# Sheet1.net
KiCad netlist of a schematic drawn in Altium Designer
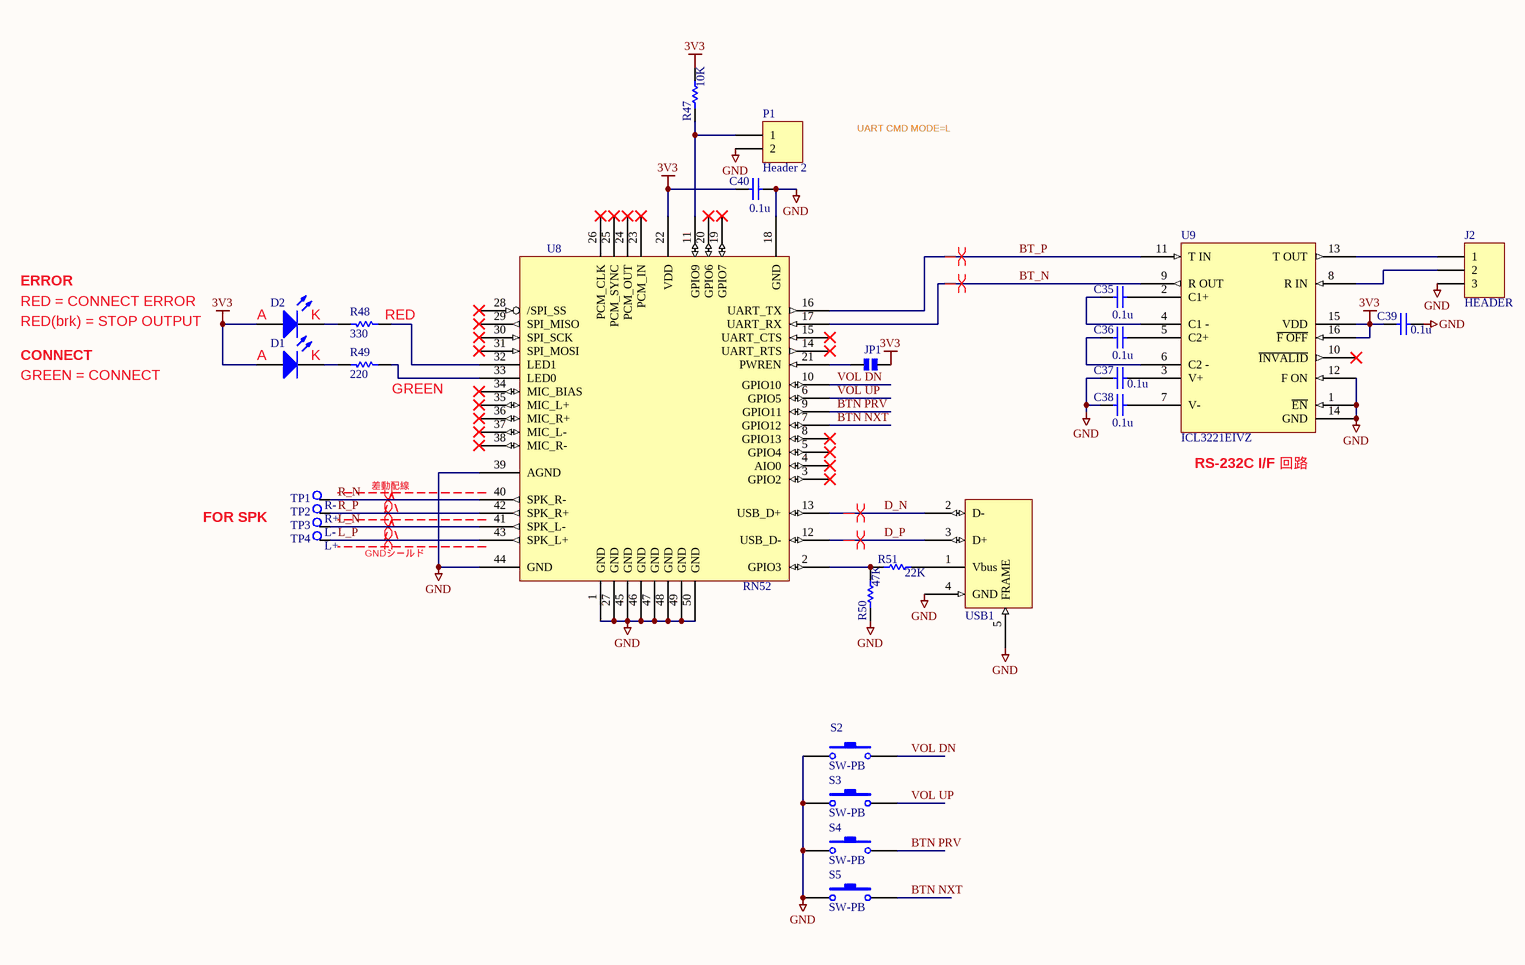
[diagram p0: Sheet1.SchDoc]

(export (version "E")
  (design (tool "Eeschema 10.0.6"))
  (components
    (comp (ref "C35")
      (value "0.1u")
      (footprint "1608[0603]")
      (description "Capacitor (Semiconductor SIM Model)")
      (fields (field (name "PUBLISHER") "Altium Limited"))
      (libsource (lib "Miscellaneous Devices") (part "Cap Semi"))
    )
    (comp (ref "C36")
      (value "0.1u")
      (footprint "1608[0603]")
      (description "Capacitor (Semiconductor SIM Model)")
      (fields (field (name "PUBLISHER") "Altium Limited"))
      (libsource (lib "Miscellaneous Devices") (part "Cap Semi"))
    )
    (comp (ref "C37")
      (value "0.1u")
      (footprint "1608[0603]")
      (description "Capacitor (Semiconductor SIM Model)")
      (fields (field (name "PUBLISHER") "Altium Limited"))
      (libsource (lib "Miscellaneous Devices") (part "Cap Semi"))
    )
    (comp (ref "C38")
      (value "0.1u")
      (footprint "1608[0603]")
      (description "Capacitor (Semiconductor SIM Model)")
      (fields (field (name "PUBLISHER") "Altium Limited"))
      (libsource (lib "Miscellaneous Devices") (part "Cap Semi"))
    )
    (comp (ref "C39")
      (value "0.1u")
      (footprint "1608[0603]")
      (description "Capacitor (Semiconductor SIM Model)")
      (fields (field (name "PUBLISHER") "Altium Limited"))
      (libsource (lib "Miscellaneous Devices") (part "Cap Semi"))
    )
    (comp (ref "C40")
      (value "0.1u")
      (footprint "1608[0603]")
      (description "Capacitor (Semiconductor SIM Model)")
      (fields (field (name "PUBLISHER") "Altium Limited"))
      (libsource (lib "Miscellaneous Devices") (part "Cap Semi"))
    )
    (comp (ref "D1")
      (value "LED2")
      (footprint "LED_2012_DIOC2012X08N")
      (description "Typical RED, GREEN, YELLOW, AMBER GaAs LED")
      (fields (field (name "PUBLISHER") "Altium Limited"))
      (libsource (lib "JP_Integrated_lib") (part "LED2"))
    )
    (comp (ref "D2")
      (value "LED2")
      (footprint "LED_2012_DIOC2012X08N")
      (description "Typical RED, GREEN, YELLOW, AMBER GaAs LED")
      (fields (field (name "PUBLISHER") "Altium Limited"))
      (libsource (lib "JP_Integrated_lib") (part "LED2"))
    )
    (comp (ref "J2")
      (value "HEADER")
      (footprint "3x 2.5mm pitch Pad")
      (description "Header, 3-Pin")
      (fields (field (name "PUBLISHER") "Altium Limited"))
      (libsource (lib "Miscellaneous Connectors") (part "Header 3"))
    )
    (comp (ref "JP1") (value "JP4") (footprint "JUMP_PAD") (libsource (lib "ORIGINAL PARTS") (part "JP4")))
    (comp (ref "P1")
      (value "Header 2")
      (footprint "2x 2.5mm pitch Pad")
      (description "Header, 2-Pin")
      (fields (field (name "PUBLISHER") "Altium Limited"))
      (libsource (lib "JP_Integrated_lib") (part "Header 2"))
    )
    (comp (ref "R47")
      (value "10K")
      (footprint "1608[0603]")
      (description "Semiconductor Resistor")
      (fields (field (name "PUBLISHER") "Altium Limited"))
      (libsource (lib "Miscellaneous Devices") (part "Res Semi"))
    )
    (comp (ref "R48")
      (value "330")
      (footprint "1608[0603]")
      (description "Resistor")
      (libsource (lib "Miscellaneous Devices") (part "Res1"))
    )
    (comp (ref "R49")
      (value "220")
      (footprint "1608[0603]")
      (description "Resistor")
      (libsource (lib "Miscellaneous Devices") (part "Res1"))
    )
    (comp (ref "R50")
      (value "47K")
      (footprint "1608[0603]")
      (description "Semiconductor Resistor")
      (fields (field (name "PUBLISHER") "Altium Limited"))
      (libsource (lib "Miscellaneous Devices") (part "Res Semi"))
    )
    (comp (ref "R51")
      (value "22K")
      (footprint "1608[0603]")
      (description "Semiconductor Resistor")
      (fields (field (name "PUBLISHER") "Altium Limited"))
      (libsource (lib "Miscellaneous Devices") (part "Res Semi"))
    )
    (comp (ref "S2")
      (value "SW-PB")
      (footprint "TACT_SW")
      (description "Switch")
      (fields (field (name "PUBLISHER") "Altium Limited"))
      (libsource (lib "JP_Integrated_lib") (part "SW-PB"))
    )
    (comp (ref "S3")
      (value "SW-PB")
      (footprint "TACT_SW")
      (description "Switch")
      (fields (field (name "PUBLISHER") "Altium Limited"))
      (libsource (lib "JP_Integrated_lib") (part "SW-PB"))
    )
    (comp (ref "S4")
      (value "SW-PB")
      (footprint "TACT_SW")
      (description "Switch")
      (fields (field (name "PUBLISHER") "Altium Limited"))
      (libsource (lib "JP_Integrated_lib") (part "SW-PB"))
    )
    (comp (ref "S5")
      (value "SW-PB")
      (footprint "TACT_SW")
      (description "Switch")
      (fields (field (name "PUBLISHER") "Altium Limited"))
      (libsource (lib "JP_Integrated_lib") (part "SW-PB"))
    )
    (comp (ref "TP1") (value "R-") (footprint "PAD1") (libsource (lib "ORIGINAL PARTS") (part "RAUND1")))
    (comp (ref "TP2") (value "R+") (footprint "PAD1") (libsource (lib "ORIGINAL PARTS") (part "RAUND1")))
    (comp (ref "TP3") (value "L-") (footprint "PAD1") (libsource (lib "ORIGINAL PARTS") (part "RAUND1")))
    (comp (ref "TP4") (value "L+") (footprint "PAD1") (libsource (lib "ORIGINAL PARTS") (part "RAUND1")))
    (comp (ref "U8") (value "RN52") (footprint "RN-52") (libsource (lib "ORIGINAL PARTS") (part "RN52")))
    (comp (ref "U9")
      (value "ICL3221EIVZ")
      (footprint "16_TSSOP_TSOP65P640X110-16N")
      (libsource (lib "ORIGINAL PARTS") (part "TRS3221E"))
    )
    (comp (ref "USB1")
      (value "USB002")
      (footprint "USB2.5-2H4C")
      (libsource (lib "ORIGINAL PARTS") (part "USB002"))
    )
  )
  (nets
    (net (code "1") (name "/BTN NXT") (class "Default")
      (node (ref "S5") (pin "2") (pinfunction "2_2") (pintype "passive"))
      (node (ref "U8") (pin "7") (pinfunction "GPIO12_7") (pintype "bidirectional"))
    )
    (net (code "2") (name "/BTN PRV") (class "Default")
      (node (ref "S4") (pin "2") (pinfunction "2_2") (pintype "passive"))
      (node (ref "U8") (pin "9") (pinfunction "GPIO11_9") (pintype "bidirectional"))
    )
    (net (code "3") (name "/BT_N") (class "Default")
      (node (ref "U8") (pin "17") (pinfunction "UART_RX_17") (pintype "input"))
      (node (ref "U9") (pin "9") (pinfunction "R_OUT_9") (pintype "output"))
    )
    (net (code "4") (name "/BT_P") (class "Default")
      (node (ref "U8") (pin "16") (pinfunction "UART_TX_16") (pintype "output"))
      (node (ref "U9") (pin "11") (pinfunction "T_IN_11") (pintype "input"))
    )
    (net (code "5") (name "/D_N") (class "Default")
      (node (ref "U8") (pin "13") (pinfunction "USB_D+_13") (pintype "bidirectional"))
      (node (ref "USB1") (pin "2") (pinfunction "D-_2") (pintype "bidirectional"))
    )
    (net (code "6") (name "/D_P") (class "Default")
      (node (ref "U8") (pin "12") (pinfunction "USB_D-_12") (pintype "bidirectional"))
      (node (ref "USB1") (pin "3") (pinfunction "D+_3") (pintype "bidirectional"))
    )
    (net (code "7") (name "/L_N") (class "Default")
      (node (ref "TP3") (pin "1") (pinfunction "1_1") (pintype "passive"))
      (node (ref "U8") (pin "41") (pinfunction "SPK_L-_41") (pintype "output"))
    )
    (net (code "8") (name "/L_P") (class "Default")
      (node (ref "TP4") (pin "1") (pinfunction "1_1") (pintype "passive"))
      (node (ref "U8") (pin "43") (pinfunction "SPK_L+_43") (pintype "output"))
    )
    (net (code "9") (name "/R_N") (class "Default")
      (node (ref "TP1") (pin "1") (pinfunction "1_1") (pintype "passive"))
      (node (ref "U8") (pin "40") (pinfunction "SPK_R-_40") (pintype "output"))
    )
    (net (code "10") (name "/R_P") (class "Default")
      (node (ref "TP2") (pin "1") (pinfunction "1_1") (pintype "passive"))
      (node (ref "U8") (pin "42") (pinfunction "SPK_R+_42") (pintype "output"))
    )
    (net (code "11") (name "/VOL DN") (class "Default")
      (node (ref "S2") (pin "2") (pinfunction "2_2") (pintype "passive"))
      (node (ref "U8") (pin "10") (pinfunction "GPIO10_10") (pintype "bidirectional"))
    )
    (net (code "12") (name "/VOL UP") (class "Default")
      (node (ref "S3") (pin "2") (pinfunction "2_2") (pintype "passive"))
      (node (ref "U8") (pin "6") (pinfunction "GPIO5_6") (pintype "bidirectional"))
    )
    (net (code "13") (name "3V3") (class "Default")
      (node (ref "C39") (pin "1") (pinfunction "1_1") (pintype "passive"))
      (node (ref "C40") (pin "1") (pinfunction "1_1") (pintype "passive"))
      (node (ref "D1") (pin "1") (pinfunction "A_1") (pintype "passive"))
      (node (ref "D2") (pin "1") (pinfunction "A_1") (pintype "passive"))
      (node (ref "JP1") (pin "2") (pinfunction "2_2") (pintype "passive"))
      (node (ref "R47") (pin "2") (pinfunction "2_2") (pintype "passive"))
      (node (ref "U8") (pin "22") (pinfunction "VDD_22") (pintype "power_in"))
      (node (ref "U9") (pin "15") (pinfunction "VDD_15") (pintype "power_in"))
      (node (ref "U9") (pin "16") (pinfunction "~{F_OFF}_16") (pintype "input"))
    )
    (net (code "14") (name "GND") (class "Default")
      (node (ref "C37") (pin "1") (pinfunction "1_1") (pintype "passive"))
      (node (ref "C38") (pin "1") (pinfunction "1_1") (pintype "passive"))
      (node (ref "C39") (pin "2") (pinfunction "2_2") (pintype "passive"))
      (node (ref "C40") (pin "2") (pinfunction "2_2") (pintype "passive"))
      (node (ref "J2") (pin "3") (pinfunction "3_3") (pintype "passive"))
      (node (ref "P1") (pin "2") (pinfunction "2_2") (pintype "passive"))
      (node (ref "R50") (pin "1") (pinfunction "1_1") (pintype "passive"))
      (node (ref "S2") (pin "1") (pinfunction "1_1") (pintype "passive"))
      (node (ref "S3") (pin "1") (pinfunction "1_1") (pintype "passive"))
      (node (ref "S4") (pin "1") (pinfunction "1_1") (pintype "passive"))
      (node (ref "S5") (pin "1") (pinfunction "1_1") (pintype "passive"))
      (node (ref "U8") (pin "1") (pinfunction "GND_1") (pintype "power_in"))
      (node (ref "U8") (pin "18") (pinfunction "GND_18") (pintype "power_in"))
      (node (ref "U8") (pin "27") (pinfunction "GND_27") (pintype "power_in"))
      (node (ref "U8") (pin "39") (pinfunction "AGND_39") (pintype "power_in"))
      (node (ref "U8") (pin "44") (pinfunction "GND_44") (pintype "power_in"))
      (node (ref "U8") (pin "45") (pinfunction "GND_45") (pintype "power_in"))
      (node (ref "U8") (pin "46") (pinfunction "GND_46") (pintype "power_in"))
      (node (ref "U8") (pin "47") (pinfunction "GND_47") (pintype "power_in"))
      (node (ref "U8") (pin "48") (pinfunction "GND_48") (pintype "power_in"))
      (node (ref "U8") (pin "49") (pinfunction "GND_49") (pintype "power_in"))
      (node (ref "U8") (pin "50") (pinfunction "GND_50") (pintype "power_in"))
      (node (ref "U9") (pin "1") (pinfunction "~{EN}_1") (pintype "input"))
      (node (ref "U9") (pin "12") (pinfunction "F_ON_12") (pintype "input"))
      (node (ref "U9") (pin "14") (pinfunction "GND_14") (pintype "power_in"))
      (node (ref "USB1") (pin "4") (pinfunction "GND_4") (pintype "input"))
      (node (ref "USB1") (pin "5") (pinfunction "FRAME_5") (pintype "input"))
    )
    (net (code "15") (name "Net-(D1-K)") (class "Default")
      (node (ref "D1") (pin "2") (pinfunction "K_2") (pintype "passive"))
      (node (ref "R49") (pin "2") (pinfunction "2_2") (pintype "passive"))
    )
    (net (code "16") (name "Net-(D2-K)") (class "Default")
      (node (ref "D2") (pin "2") (pinfunction "K_2") (pintype "passive"))
      (node (ref "R48") (pin "2") (pinfunction "2_2") (pintype "passive"))
    )
    (net (code "17") (name "Net-(U8-GPIO3)") (class "Default")
      (node (ref "R50") (pin "2") (pinfunction "2_2") (pintype "passive"))
      (node (ref "R51") (pin "2") (pinfunction "2_2") (pintype "passive"))
      (node (ref "U8") (pin "2") (pinfunction "GPIO3_2") (pintype "bidirectional"))
    )
    (net (code "18") (name "Net-(U8-GPIO9)") (class "Default")
      (node (ref "P1") (pin "1") (pinfunction "1_1") (pintype "passive"))
      (node (ref "R47") (pin "1") (pinfunction "1_1") (pintype "passive"))
      (node (ref "U8") (pin "11") (pinfunction "GPIO9_11") (pintype "bidirectional"))
    )
    (net (code "19") (name "Net-(U8-LED0)") (class "Default")
      (node (ref "R49") (pin "1") (pinfunction "1_1") (pintype "passive"))
      (node (ref "U8") (pin "33") (pinfunction "LED0_33") (pintype "passive"))
    )
    (net (code "20") (name "Net-(U8-LED1)") (class "Default")
      (node (ref "R48") (pin "1") (pinfunction "1_1") (pintype "passive"))
      (node (ref "U8") (pin "32") (pinfunction "LED1_32") (pintype "passive"))
    )
    (net (code "21") (name "Net-(U8-PWREN)") (class "Default")
      (node (ref "JP1") (pin "1") (pinfunction "1_1") (pintype "passive"))
      (node (ref "U8") (pin "21") (pinfunction "PWREN_21") (pintype "input"))
    )
    (net (code "22") (name "Net-(U9-C1+)") (class "Default")
      (node (ref "C35") (pin "2") (pinfunction "2_2") (pintype "passive"))
      (node (ref "U9") (pin "2") (pinfunction "C1+_2") (pintype "passive"))
    )
    (net (code "23") (name "Net-(U9-C1_-)") (class "Default")
      (node (ref "C35") (pin "1") (pinfunction "1_1") (pintype "passive"))
      (node (ref "U9") (pin "4") (pinfunction "C1_-_4") (pintype "passive"))
    )
    (net (code "24") (name "Net-(U9-C2+)") (class "Default")
      (node (ref "C36") (pin "2") (pinfunction "2_2") (pintype "passive"))
      (node (ref "U9") (pin "5") (pinfunction "C2+_5") (pintype "passive"))
    )
    (net (code "25") (name "Net-(U9-C2_-)") (class "Default")
      (node (ref "C36") (pin "1") (pinfunction "1_1") (pintype "passive"))
      (node (ref "U9") (pin "6") (pinfunction "C2_-_6") (pintype "passive"))
    )
    (net (code "26") (name "Net-(U9-R_IN)") (class "Default")
      (node (ref "J2") (pin "2") (pinfunction "2_2") (pintype "passive"))
      (node (ref "U9") (pin "8") (pinfunction "R_IN_8") (pintype "input"))
    )
    (net (code "27") (name "Net-(U9-T_OUT)") (class "Default")
      (node (ref "J2") (pin "1") (pinfunction "1_1") (pintype "passive"))
      (node (ref "U9") (pin "13") (pinfunction "T_OUT_13") (pintype "output"))
    )
    (net (code "28") (name "Net-(U9-V+)") (class "Default")
      (node (ref "C37") (pin "2") (pinfunction "2_2") (pintype "passive"))
      (node (ref "U9") (pin "3") (pinfunction "V+_3") (pintype "power_in"))
    )
    (net (code "29") (name "Net-(U9-V-)") (class "Default")
      (node (ref "C38") (pin "2") (pinfunction "2_2") (pintype "passive"))
      (node (ref "U9") (pin "7") (pinfunction "V-_7") (pintype "power_in"))
    )
    (net (code "30") (name "Net-(USB1-Vbus)") (class "Default")
      (node (ref "R51") (pin "1") (pinfunction "1_1") (pintype "passive"))
      (node (ref "USB1") (pin "1") (pinfunction "Vbus_1") (pintype "power_in"))
    )
    (net (code "31") (name "unconnected-(U8-AIO0-Pad4)") (class "Default")
      (node (ref "U8") (pin "4") (pinfunction "AIO0_4") (pintype "bidirectional+no_connect"))
    )
    (net (code "32") (name "unconnected-(U8-GPIO2-Pad3)") (class "Default")
      (node (ref "U8") (pin "3") (pinfunction "GPIO2_3") (pintype "bidirectional+no_connect"))
    )
    (net (code "33") (name "unconnected-(U8-GPIO4-Pad5)") (class "Default")
      (node (ref "U8") (pin "5") (pinfunction "GPIO4_5") (pintype "bidirectional+no_connect"))
    )
    (net (code "34") (name "unconnected-(U8-GPIO6-Pad20)") (class "Default")
      (node (ref "U8") (pin "20") (pinfunction "GPIO6_20") (pintype "bidirectional+no_connect"))
    )
    (net (code "35") (name "unconnected-(U8-GPIO7-Pad19)") (class "Default")
      (node (ref "U8") (pin "19") (pinfunction "GPIO7_19") (pintype "bidirectional+no_connect"))
    )
    (net (code "36") (name "unconnected-(U8-GPIO13-Pad8)") (class "Default")
      (node (ref "U8") (pin "8") (pinfunction "GPIO13_8") (pintype "bidirectional+no_connect"))
    )
    (net (code "37") (name "unconnected-(U8-MIC_BIAS-Pad34)") (class "Default")
      (node (ref "U8") (pin "34") (pinfunction "MIC_BIAS_34") (pintype "bidirectional+no_connect"))
    )
    (net (code "38") (name "unconnected-(U8-MIC_L+-Pad35)") (class "Default")
      (node (ref "U8") (pin "35") (pinfunction "MIC_L+_35") (pintype "bidirectional+no_connect"))
    )
    (net (code "39") (name "unconnected-(U8-MIC_L--Pad37)") (class "Default")
      (node (ref "U8") (pin "37") (pinfunction "MIC_L-_37") (pintype "bidirectional+no_connect"))
    )
    (net (code "40") (name "unconnected-(U8-MIC_R+-Pad36)") (class "Default")
      (node (ref "U8") (pin "36") (pinfunction "MIC_R+_36") (pintype "bidirectional+no_connect"))
    )
    (net (code "41") (name "unconnected-(U8-MIC_R--Pad38)") (class "Default")
      (node (ref "U8") (pin "38") (pinfunction "MIC_R-_38") (pintype "bidirectional+no_connect"))
    )
    (net (code "42") (name "unconnected-(U8-PCM_CLK-Pad26)") (class "Default")
      (node (ref "U8") (pin "26") (pinfunction "PCM_CLK_26") (pintype "passive+no_connect"))
    )
    (net (code "43") (name "unconnected-(U8-PCM_IN-Pad23)") (class "Default")
      (node (ref "U8") (pin "23") (pinfunction "PCM_IN_23") (pintype "passive+no_connect"))
    )
    (net (code "44") (name "unconnected-(U8-PCM_OUT-Pad24)") (class "Default")
      (node (ref "U8") (pin "24") (pinfunction "PCM_OUT_24") (pintype "passive+no_connect"))
    )
    (net (code "45") (name "unconnected-(U8-PCM_SYNC-Pad25)") (class "Default")
      (node (ref "U8") (pin "25") (pinfunction "PCM_SYNC_25") (pintype "passive+no_connect"))
    )
    (net (code "46") (name "unconnected-(U8-SPI_MISO-Pad29)") (class "Default")
      (node (ref "U8") (pin "29") (pinfunction "SPI_MISO_29") (pintype "output+no_connect"))
    )
    (net (code "47") (name "unconnected-(U8-SPI_MOSI-Pad31)") (class "Default")
      (node (ref "U8") (pin "31") (pinfunction "SPI_MOSI_31") (pintype "input+no_connect"))
    )
    (net (code "48") (name "unconnected-(U8-SPI_SCK-Pad30)") (class "Default")
      (node (ref "U8") (pin "30") (pinfunction "SPI_SCK_30") (pintype "input+no_connect"))
    )
    (net (code "49") (name "unconnected-(U8-UART_CTS-Pad15)") (class "Default")
      (node (ref "U8") (pin "15") (pinfunction "UART_CTS_15") (pintype "input+no_connect"))
    )
    (net (code "50") (name "unconnected-(U8-UART_RTS-Pad14)") (class "Default")
      (node (ref "U8") (pin "14") (pinfunction "UART_RTS_14") (pintype "output+no_connect"))
    )
    (net (code "51") (name "unconnected-(U8-{slash}SPI_SS-Pad28)") (class "Default")
      (node (ref "U8") (pin "28") (pinfunction "/SPI_SS_28") (pintype "input+no_connect"))
    )
    (net (code "52") (name "unconnected-(U9-~{INVALID}-Pad10)") (class "Default")
      (node (ref "U9") (pin "10") (pinfunction "~{INVALID}_10") (pintype "output+no_connect"))
    )
  )
)
